# qstp_q2.net
KiCad netlist of a schematic drawn in EAGLE
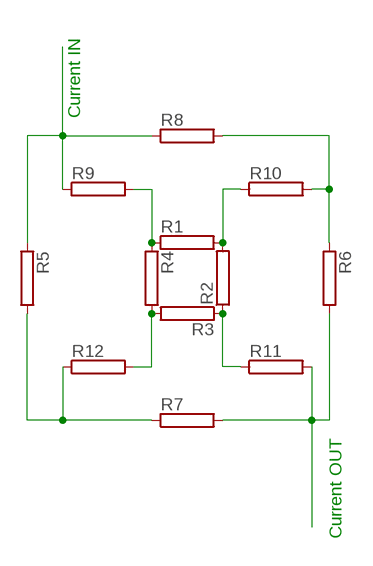
[diagram p0: schematic, sheet 1]

(export (version "E")
  (design (tool "Eeschema 10.0.6"))
  (components
    (comp (ref "R1")
      (value "RAC01")
      (footprint "eagle-import:AC01")
      (libsource (lib "eagle-import") (part "RAC01"))
    )
    (comp (ref "R2")
      (value "RAC01")
      (footprint "eagle-import:AC01")
      (libsource (lib "eagle-import") (part "RAC01"))
    )
    (comp (ref "R3")
      (value "RAC01")
      (footprint "eagle-import:AC01")
      (libsource (lib "eagle-import") (part "RAC01"))
    )
    (comp (ref "R4")
      (value "RAC01")
      (footprint "eagle-import:AC01")
      (libsource (lib "eagle-import") (part "RAC01"))
    )
    (comp (ref "R5")
      (value "RAC01")
      (footprint "eagle-import:AC01")
      (libsource (lib "eagle-import") (part "RAC01"))
    )
    (comp (ref "R6")
      (value "RAC01")
      (footprint "eagle-import:AC01")
      (libsource (lib "eagle-import") (part "RAC01"))
    )
    (comp (ref "R7")
      (value "RAC01")
      (footprint "eagle-import:AC01")
      (libsource (lib "eagle-import") (part "RAC01"))
    )
    (comp (ref "R8")
      (value "RAC01")
      (footprint "eagle-import:AC01")
      (libsource (lib "eagle-import") (part "RAC01"))
    )
    (comp (ref "R9")
      (value "RAC01")
      (footprint "eagle-import:AC01")
      (libsource (lib "eagle-import") (part "RAC01"))
    )
    (comp (ref "R10")
      (value "RAC01")
      (footprint "eagle-import:AC01")
      (libsource (lib "eagle-import") (part "RAC01"))
    )
    (comp (ref "R11")
      (value "RAC01")
      (footprint "eagle-import:AC01")
      (libsource (lib "eagle-import") (part "RAC01"))
    )
    (comp (ref "R12")
      (value "RAC01")
      (footprint "eagle-import:AC01")
      (libsource (lib "eagle-import") (part "RAC01"))
    )
  )
  (nets
    (net (code "1") (name "Net-(R1-Pad1)") (class "Default")
      (node (ref "R1") (pin "1") (pinfunction "1_1") (pintype "passive"))
      (node (ref "R4") (pin "1") (pinfunction "1_1") (pintype "passive"))
      (node (ref "R9") (pin "2") (pinfunction "2_2") (pintype "passive"))
    )
    (net (code "2") (name "Net-(R1-Pad2)") (class "Default")
      (node (ref "R1") (pin "2") (pinfunction "2_2") (pintype "passive"))
      (node (ref "R10") (pin "1") (pinfunction "1_1") (pintype "passive"))
      (node (ref "R2") (pin "2") (pinfunction "2_2") (pintype "passive"))
    )
    (net (code "3") (name "Net-(R5-Pad1)") (class "Default")
      (node (ref "R5") (pin "1") (pinfunction "1_1") (pintype "passive"))
      (node (ref "R8") (pin "1") (pinfunction "1_1") (pintype "passive"))
      (node (ref "R9") (pin "1") (pinfunction "1_1") (pintype "passive"))
    )
    (net (code "4") (name "Net-(R10-Pad2)") (class "Default")
      (node (ref "R10") (pin "2") (pinfunction "2_2") (pintype "passive"))
      (node (ref "R6") (pin "1") (pinfunction "1_1") (pintype "passive"))
      (node (ref "R8") (pin "2") (pinfunction "2_2") (pintype "passive"))
    )
    (net (code "5") (name "Net-(R11-Pad1)") (class "Default")
      (node (ref "R11") (pin "1") (pinfunction "1_1") (pintype "passive"))
      (node (ref "R2") (pin "1") (pinfunction "1_1") (pintype "passive"))
      (node (ref "R3") (pin "1") (pinfunction "1_1") (pintype "passive"))
    )
    (net (code "6") (name "Net-(R11-Pad2)") (class "Default")
      (node (ref "R11") (pin "2") (pinfunction "2_2") (pintype "passive"))
      (node (ref "R6") (pin "2") (pinfunction "2_2") (pintype "passive"))
      (node (ref "R7") (pin "2") (pinfunction "2_2") (pintype "passive"))
    )
    (net (code "7") (name "Net-(R12-Pad1)") (class "Default")
      (node (ref "R12") (pin "1") (pinfunction "1_1") (pintype "passive"))
      (node (ref "R5") (pin "2") (pinfunction "2_2") (pintype "passive"))
      (node (ref "R7") (pin "1") (pinfunction "1_1") (pintype "passive"))
    )
    (net (code "8") (name "Net-(R12-Pad2)") (class "Default")
      (node (ref "R12") (pin "2") (pinfunction "2_2") (pintype "passive"))
      (node (ref "R3") (pin "2") (pinfunction "2_2") (pintype "passive"))
      (node (ref "R4") (pin "2") (pinfunction "2_2") (pintype "passive"))
    )
  )
)
